# adc.net
KiCad netlist of a schematic drawn in Altium Designer
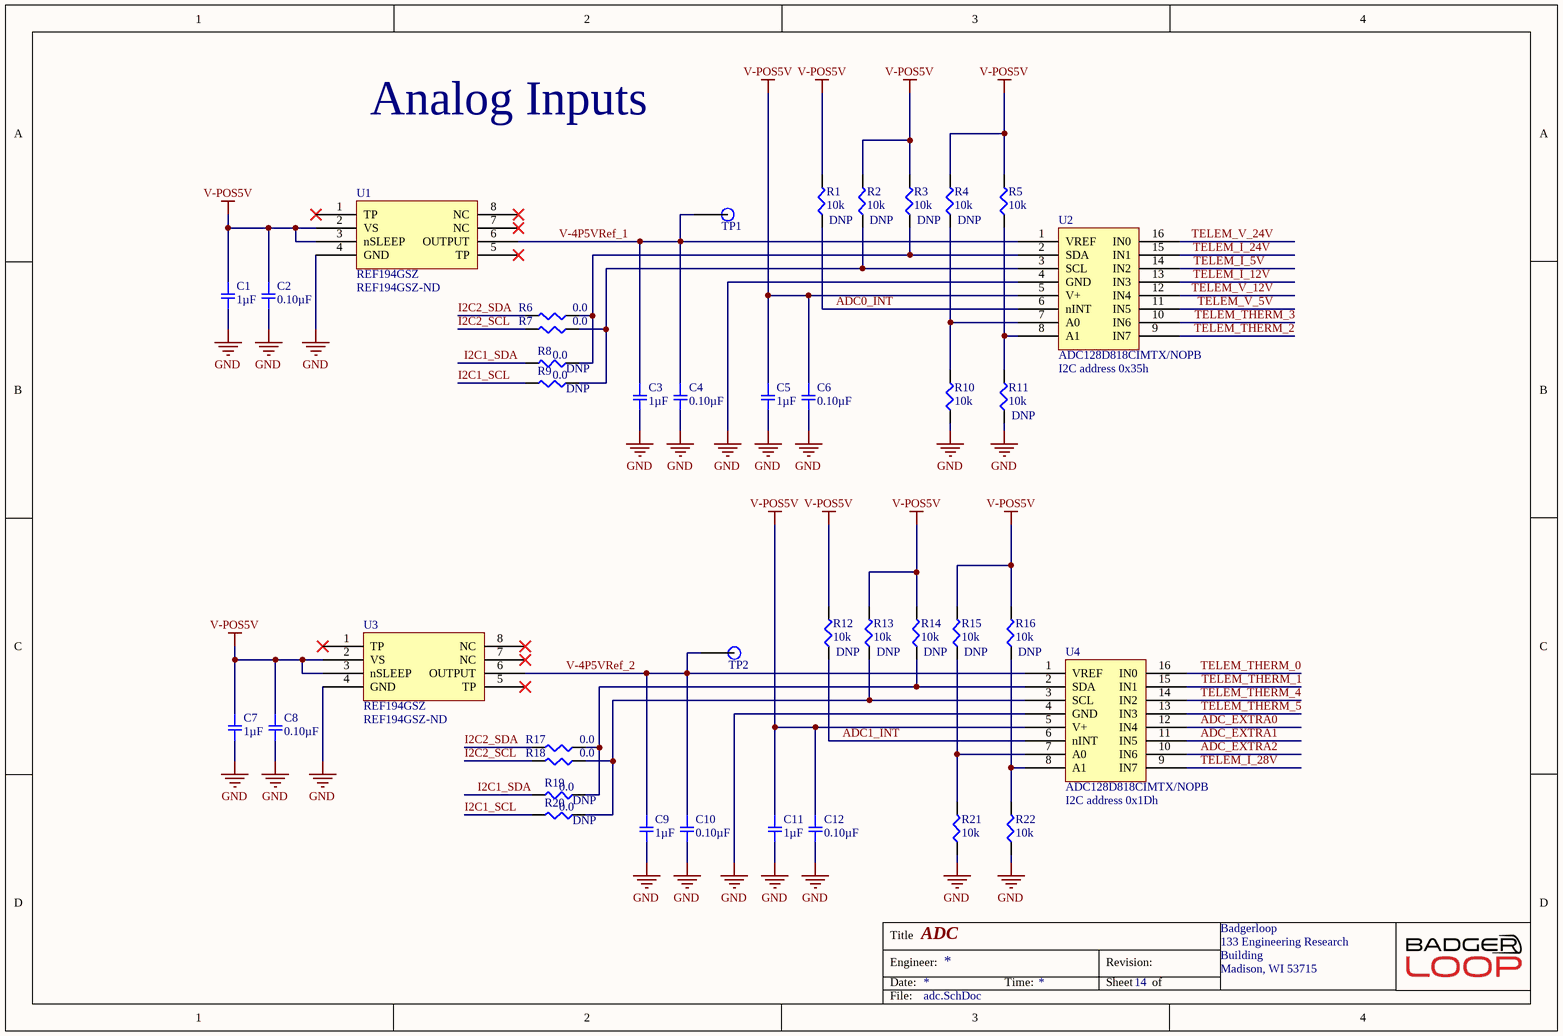
[diagram p0: adc.SchDoc]

(export (version "E")
  (design (tool "Eeschema 10.0.6"))
  (components
    (comp (ref "C1")
      (value "1µF")
      (footprint "SMD-0805C")
      (description "CAP CER 1UF 50V X7R 0805")
      (fields
        (field (name "DIGI-KEY PART NUMBER") "490-4736-1-ND")
        (field (name "PART NUMBER") "GRM21BR71H105KA12L")
      )
      (libsource (lib "capacitors") (part "GRM21BR71H105KA12L"))
    )
    (comp (ref "C2")
      (value "0.10µF")
      (footprint "SMD-0805C")
      (description "CAP CER 0.1UF 50V X7R 0805")
      (fields
        (field (name "DIGI-KEY PART NUMBER") "490-11955-1-ND")
        (field (name "PART NUMBER") "GCD21BR71H104KA01L")
      )
      (libsource (lib "capacitors") (part "GCD21BR71H104KA01L"))
    )
    (comp (ref "C3")
      (value "1µF")
      (footprint "SMD-0805C")
      (description "CAP CER 1UF 50V X7R 0805")
      (fields
        (field (name "DIGI-KEY PART NUMBER") "490-4736-1-ND")
        (field (name "PART NUMBER") "GRM21BR71H105KA12L")
      )
      (libsource (lib "capacitors") (part "GRM21BR71H105KA12L"))
    )
    (comp (ref "C4")
      (value "0.10µF")
      (footprint "SMD-0805C")
      (description "CAP CER 0.1UF 50V X7R 0805")
      (fields
        (field (name "DIGI-KEY PART NUMBER") "490-11955-1-ND")
        (field (name "PART NUMBER") "GCD21BR71H104KA01L")
      )
      (libsource (lib "capacitors") (part "GCD21BR71H104KA01L"))
    )
    (comp (ref "C5")
      (value "1µF")
      (footprint "SMD-0805C")
      (description "CAP CER 1UF 50V X7R 0805")
      (fields
        (field (name "DIGI-KEY PART NUMBER") "490-4736-1-ND")
        (field (name "PART NUMBER") "GRM21BR71H105KA12L")
      )
      (libsource (lib "capacitors") (part "GRM21BR71H105KA12L"))
    )
    (comp (ref "C6")
      (value "0.10µF")
      (footprint "SMD-0805C")
      (description "CAP CER 0.1UF 50V X7R 0805")
      (fields
        (field (name "DIGI-KEY PART NUMBER") "490-11955-1-ND")
        (field (name "PART NUMBER") "GCD21BR71H104KA01L")
      )
      (libsource (lib "capacitors") (part "GCD21BR71H104KA01L"))
    )
    (comp (ref "C7")
      (value "1µF")
      (footprint "SMD-0805C")
      (description "CAP CER 1UF 50V X7R 0805")
      (fields
        (field (name "DIGI-KEY PART NUMBER") "490-4736-1-ND")
        (field (name "PART NUMBER") "GRM21BR71H105KA12L")
      )
      (libsource (lib "capacitors") (part "GRM21BR71H105KA12L"))
    )
    (comp (ref "C8")
      (value "0.10µF")
      (footprint "SMD-0805C")
      (description "CAP CER 0.1UF 50V X7R 0805")
      (fields
        (field (name "DIGI-KEY PART NUMBER") "490-11955-1-ND")
        (field (name "PART NUMBER") "GCD21BR71H104KA01L")
      )
      (libsource (lib "capacitors") (part "GCD21BR71H104KA01L"))
    )
    (comp (ref "C9")
      (value "1µF")
      (footprint "SMD-0805C")
      (description "CAP CER 1UF 50V X7R 0805")
      (fields
        (field (name "DIGI-KEY PART NUMBER") "490-4736-1-ND")
        (field (name "PART NUMBER") "GRM21BR71H105KA12L")
      )
      (libsource (lib "capacitors") (part "GRM21BR71H105KA12L"))
    )
    (comp (ref "C10")
      (value "0.10µF")
      (footprint "SMD-0805C")
      (description "CAP CER 0.1UF 50V X7R 0805")
      (fields
        (field (name "DIGI-KEY PART NUMBER") "490-11955-1-ND")
        (field (name "PART NUMBER") "GCD21BR71H104KA01L")
      )
      (libsource (lib "capacitors") (part "GCD21BR71H104KA01L"))
    )
    (comp (ref "C11")
      (value "1µF")
      (footprint "SMD-0805C")
      (description "CAP CER 1UF 50V X7R 0805")
      (fields
        (field (name "DIGI-KEY PART NUMBER") "490-4736-1-ND")
        (field (name "PART NUMBER") "GRM21BR71H105KA12L")
      )
      (libsource (lib "capacitors") (part "GRM21BR71H105KA12L"))
    )
    (comp (ref "C12")
      (value "0.10µF")
      (footprint "SMD-0805C")
      (description "CAP CER 0.1UF 50V X7R 0805")
      (fields
        (field (name "DIGI-KEY PART NUMBER") "490-11955-1-ND")
        (field (name "PART NUMBER") "GCD21BR71H104KA01L")
      )
      (libsource (lib "capacitors") (part "GCD21BR71H104KA01L"))
    )
    (comp (ref "R1")
      (value "10k")
      (footprint "SMD-0805-RES")
      (description "RES SMD 10K OHM 5% 1/2W 0805")
      (fields
        (field (name "PART NUMBER") "ERJ-P06J103V")
        (field (name "DIGI-KEY PART NUMBER") "P10KADCT-ND")
        (field (name "DNP") "DNP")
      )
      (libsource (lib "resistors") (part "ERJ-P06J103V"))
    )
    (comp (ref "R2")
      (value "10k")
      (footprint "SMD-0805-RES")
      (description "RES SMD 10K OHM 5% 1/2W 0805")
      (fields
        (field (name "PART NUMBER") "ERJ-P06J103V")
        (field (name "DIGI-KEY PART NUMBER") "P10KADCT-ND")
        (field (name "DNP") "DNP")
      )
      (libsource (lib "resistors") (part "ERJ-P06J103V"))
    )
    (comp (ref "R3")
      (value "10k")
      (footprint "SMD-0805-RES")
      (description "RES SMD 10K OHM 5% 1/2W 0805")
      (fields
        (field (name "PART NUMBER") "ERJ-P06J103V")
        (field (name "DIGI-KEY PART NUMBER") "P10KADCT-ND")
        (field (name "DNP") "DNP")
      )
      (libsource (lib "resistors") (part "ERJ-P06J103V"))
    )
    (comp (ref "R4")
      (value "10k")
      (footprint "SMD-0805-RES")
      (description "RES SMD 10K OHM 5% 1/2W 0805")
      (fields
        (field (name "PART NUMBER") "ERJ-P06J103V")
        (field (name "DIGI-KEY PART NUMBER") "P10KADCT-ND")
        (field (name "DNP") "DNP")
      )
      (libsource (lib "resistors") (part "ERJ-P06J103V"))
    )
    (comp (ref "R5")
      (value "10k")
      (footprint "SMD-0805-RES")
      (description "RES SMD 10K OHM 5% 1/2W 0805")
      (fields (field (name "PART NUMBER") "ERJ-P06J103V") (field (name "DIGI-KEY PART NUMBER") "P10KADCT-ND"))
      (libsource (lib "resistors") (part "ERJ-P06J103V"))
    )
    (comp (ref "R6")
      (value "0.0")
      (footprint "SMD-0805-RES")
      (description "RES SMD 0.0 OHM JUMPER 1/8W 0805")
      (fields (field (name "PART NUMBER") "ERJ-6GEY0R00V") (field (name "DIGI-KEY PART NUMBER") "P0.0ACT-ND"))
      (libsource (lib "resistors") (part "ERJ-6GEY0R00V"))
    )
    (comp (ref "R7")
      (value "0.0")
      (footprint "SMD-0805-RES")
      (description "RES SMD 0.0 OHM JUMPER 1/8W 0805")
      (fields (field (name "PART NUMBER") "ERJ-6GEY0R00V") (field (name "DIGI-KEY PART NUMBER") "P0.0ACT-ND"))
      (libsource (lib "resistors") (part "ERJ-6GEY0R00V"))
    )
    (comp (ref "R8")
      (value "0.0")
      (footprint "SMD-0805-RES")
      (description "RES SMD 0.0 OHM JUMPER 1/8W 0805")
      (fields
        (field (name "PART NUMBER") "ERJ-6GEY0R00V")
        (field (name "DIGI-KEY PART NUMBER") "P0.0ACT-ND")
        (field (name "DNP") "DNP")
      )
      (libsource (lib "resistors") (part "ERJ-6GEY0R00V"))
    )
    (comp (ref "R9")
      (value "0.0")
      (footprint "SMD-0805-RES")
      (description "RES SMD 0.0 OHM JUMPER 1/8W 0805")
      (fields
        (field (name "PART NUMBER") "ERJ-6GEY0R00V")
        (field (name "DIGI-KEY PART NUMBER") "P0.0ACT-ND")
        (field (name "DNP") "DNP")
      )
      (libsource (lib "resistors") (part "ERJ-6GEY0R00V"))
    )
    (comp (ref "R10")
      (value "10k")
      (footprint "SMD-0805-RES")
      (description "RES SMD 10K OHM 5% 1/2W 0805")
      (fields (field (name "PART NUMBER") "ERJ-P06J103V") (field (name "DIGI-KEY PART NUMBER") "P10KADCT-ND"))
      (libsource (lib "resistors") (part "ERJ-P06J103V"))
    )
    (comp (ref "R11")
      (value "10k")
      (footprint "SMD-0805-RES")
      (description "RES SMD 10K OHM 5% 1/2W 0805")
      (fields
        (field (name "PART NUMBER") "ERJ-P06J103V")
        (field (name "DIGI-KEY PART NUMBER") "P10KADCT-ND")
        (field (name "DNP") "DNP")
      )
      (libsource (lib "resistors") (part "ERJ-P06J103V"))
    )
    (comp (ref "R12")
      (value "10k")
      (footprint "SMD-0805-RES")
      (description "RES SMD 10K OHM 5% 1/2W 0805")
      (fields
        (field (name "PART NUMBER") "ERJ-P06J103V")
        (field (name "DIGI-KEY PART NUMBER") "P10KADCT-ND")
        (field (name "DNP") "DNP")
      )
      (libsource (lib "resistors") (part "ERJ-P06J103V"))
    )
    (comp (ref "R13")
      (value "10k")
      (footprint "SMD-0805-RES")
      (description "RES SMD 10K OHM 5% 1/2W 0805")
      (fields
        (field (name "PART NUMBER") "ERJ-P06J103V")
        (field (name "DIGI-KEY PART NUMBER") "P10KADCT-ND")
        (field (name "DNP") "DNP")
      )
      (libsource (lib "resistors") (part "ERJ-P06J103V"))
    )
    (comp (ref "R14")
      (value "10k")
      (footprint "SMD-0805-RES")
      (description "RES SMD 10K OHM 5% 1/2W 0805")
      (fields
        (field (name "PART NUMBER") "ERJ-P06J103V")
        (field (name "DIGI-KEY PART NUMBER") "P10KADCT-ND")
        (field (name "DNP") "DNP")
      )
      (libsource (lib "resistors") (part "ERJ-P06J103V"))
    )
    (comp (ref "R15")
      (value "10k")
      (footprint "SMD-0805-RES")
      (description "RES SMD 10K OHM 5% 1/2W 0805")
      (fields
        (field (name "PART NUMBER") "ERJ-P06J103V")
        (field (name "DIGI-KEY PART NUMBER") "P10KADCT-ND")
        (field (name "DNP") "DNP")
      )
      (libsource (lib "resistors") (part "ERJ-P06J103V"))
    )
    (comp (ref "R16")
      (value "10k")
      (footprint "SMD-0805-RES")
      (description "RES SMD 10K OHM 5% 1/2W 0805")
      (fields
        (field (name "PART NUMBER") "ERJ-P06J103V")
        (field (name "DIGI-KEY PART NUMBER") "P10KADCT-ND")
        (field (name "DNP") "DNP")
      )
      (libsource (lib "resistors") (part "ERJ-P06J103V"))
    )
    (comp (ref "R17")
      (value "0.0")
      (footprint "SMD-0805-RES")
      (description "RES SMD 0.0 OHM JUMPER 1/8W 0805")
      (fields (field (name "PART NUMBER") "ERJ-6GEY0R00V") (field (name "DIGI-KEY PART NUMBER") "P0.0ACT-ND"))
      (libsource (lib "resistors") (part "ERJ-6GEY0R00V"))
    )
    (comp (ref "R18")
      (value "0.0")
      (footprint "SMD-0805-RES")
      (description "RES SMD 0.0 OHM JUMPER 1/8W 0805")
      (fields (field (name "PART NUMBER") "ERJ-6GEY0R00V") (field (name "DIGI-KEY PART NUMBER") "P0.0ACT-ND"))
      (libsource (lib "resistors") (part "ERJ-6GEY0R00V"))
    )
    (comp (ref "R19")
      (value "0.0")
      (footprint "SMD-0805-RES")
      (description "RES SMD 0.0 OHM JUMPER 1/8W 0805")
      (fields
        (field (name "PART NUMBER") "ERJ-6GEY0R00V")
        (field (name "DIGI-KEY PART NUMBER") "P0.0ACT-ND")
        (field (name "DNP") "DNP")
      )
      (libsource (lib "resistors") (part "ERJ-6GEY0R00V"))
    )
    (comp (ref "R20")
      (value "0.0")
      (footprint "SMD-0805-RES")
      (description "RES SMD 0.0 OHM JUMPER 1/8W 0805")
      (fields
        (field (name "PART NUMBER") "ERJ-6GEY0R00V")
        (field (name "DIGI-KEY PART NUMBER") "P0.0ACT-ND")
        (field (name "DNP") "DNP")
      )
      (libsource (lib "resistors") (part "ERJ-6GEY0R00V"))
    )
    (comp (ref "R21")
      (value "10k")
      (footprint "SMD-0805-RES")
      (description "RES SMD 10K OHM 5% 1/2W 0805")
      (fields (field (name "PART NUMBER") "ERJ-P06J103V") (field (name "DIGI-KEY PART NUMBER") "P10KADCT-ND"))
      (libsource (lib "resistors") (part "ERJ-P06J103V"))
    )
    (comp (ref "R22")
      (value "10k")
      (footprint "SMD-0805-RES")
      (description "RES SMD 10K OHM 5% 1/2W 0805")
      (fields (field (name "PART NUMBER") "ERJ-P06J103V") (field (name "DIGI-KEY PART NUMBER") "P10KADCT-ND"))
      (libsource (lib "resistors") (part "ERJ-P06J103V"))
    )
    (comp (ref "TP1")
      (value "TP")
      (footprint "Test Point")
      (description "SMD TEST POINT")
      (libsource (lib "misc") (part "TP"))
    )
    (comp (ref "TP2")
      (value "TP")
      (footprint "Test Point")
      (description "SMD TEST POINT")
      (libsource (lib "misc") (part "TP"))
    )
    (comp (ref "U1")
      (value "REF194GSZ")
      (footprint "SOP127P600X175-8N")
      (description "IC VREF SERIES 4.5V 8SOIC")
      (fields
        (field (name "MANUFACTURER") "Analog Devices")
        (field (name "SUPPLIER PART NUMBER 1") "REF194GSZ-ND")
      )
      (libsource (lib "ic") (part "REF194GSZ"))
    )
    (comp (ref "U2")
      (value "ADC128D818CIMTX/NOPB")
      (footprint "TSOP65P660X120-16N")
      (description "Analog to Digital Converters - ADC")
      (fields (field (name "MANUFACTURER") "TI National Semiconductor"))
      (libsource (lib "ic") (part "ADC128D818CIMTX/NOPB"))
    )
    (comp (ref "U3")
      (value "REF194GSZ")
      (footprint "SOP127P600X175-8N")
      (description "IC VREF SERIES 4.5V 8SOIC")
      (fields
        (field (name "MANUFACTURER") "Analog Devices")
        (field (name "SUPPLIER PART NUMBER 1") "REF194GSZ-ND")
      )
      (libsource (lib "ic") (part "REF194GSZ"))
    )
    (comp (ref "U4")
      (value "ADC128D818CIMTX/NOPB")
      (footprint "TSOP65P660X120-16N")
      (description "Analog to Digital Converters - ADC")
      (fields (field (name "MANUFACTURER") "TI National Semiconductor"))
      (libsource (lib "ic") (part "ADC128D818CIMTX/NOPB"))
    )
  )
  (nets
    (net (code "1") (name "/ADC0_INT") (class "Default")
      (node (ref "R1") (pin "1") (pinfunction "1_1") (pintype "passive"))
      (node (ref "U2") (pin "6") (pinfunction "nINT_6") (pintype "passive"))
    )
    (net (code "2") (name "/ADC1_INT") (class "Default")
      (node (ref "R12") (pin "1") (pinfunction "1_1") (pintype "passive"))
      (node (ref "U4") (pin "6") (pinfunction "nINT_6") (pintype "passive"))
    )
    (net (code "3") (name "/ADC_EXTRA0") (class "Default")
      (node (ref "U4") (pin "12") (pinfunction "IN4_12") (pintype "passive"))
    )
    (net (code "4") (name "/ADC_EXTRA1") (class "Default")
      (node (ref "U4") (pin "11") (pinfunction "IN5_11") (pintype "passive"))
    )
    (net (code "5") (name "/ADC_EXTRA2") (class "Default")
      (node (ref "U4") (pin "10") (pinfunction "IN6_10") (pintype "passive"))
    )
    (net (code "6") (name "/I2C1_SCL") (class "Default")
      (node (ref "R20") (pin "2") (pinfunction "2_2") (pintype "passive"))
      (node (ref "R9") (pin "2") (pinfunction "2_2") (pintype "passive"))
    )
    (net (code "7") (name "/I2C1_SDA") (class "Default")
      (node (ref "R19") (pin "2") (pinfunction "2_2") (pintype "passive"))
      (node (ref "R8") (pin "2") (pinfunction "2_2") (pintype "passive"))
    )
    (net (code "8") (name "/I2C2_SCL") (class "Default")
      (node (ref "R18") (pin "2") (pinfunction "2_2") (pintype "passive"))
      (node (ref "R7") (pin "2") (pinfunction "2_2") (pintype "passive"))
    )
    (net (code "9") (name "/I2C2_SDA") (class "Default")
      (node (ref "R17") (pin "2") (pinfunction "2_2") (pintype "passive"))
      (node (ref "R6") (pin "2") (pinfunction "2_2") (pintype "passive"))
    )
    (net (code "10") (name "/TELEM_I_5V") (class "Default")
      (node (ref "U2") (pin "14") (pinfunction "IN2_14") (pintype "passive"))
    )
    (net (code "11") (name "/TELEM_I_12V") (class "Default")
      (node (ref "U2") (pin "13") (pinfunction "IN3_13") (pintype "passive"))
    )
    (net (code "12") (name "/TELEM_I_24V") (class "Default")
      (node (ref "U2") (pin "15") (pinfunction "IN1_15") (pintype "passive"))
    )
    (net (code "13") (name "/TELEM_I_28V") (class "Default")
      (node (ref "U4") (pin "9") (pinfunction "IN7_9") (pintype "passive"))
    )
    (net (code "14") (name "/TELEM_THERM_0") (class "Default")
      (node (ref "U4") (pin "16") (pinfunction "IN0_16") (pintype "passive"))
    )
    (net (code "15") (name "/TELEM_THERM_1") (class "Default")
      (node (ref "U4") (pin "15") (pinfunction "IN1_15") (pintype "passive"))
    )
    (net (code "16") (name "/TELEM_THERM_2") (class "Default")
      (node (ref "U2") (pin "9") (pinfunction "IN7_9") (pintype "passive"))
    )
    (net (code "17") (name "/TELEM_THERM_3") (class "Default")
      (node (ref "U2") (pin "10") (pinfunction "IN6_10") (pintype "passive"))
    )
    (net (code "18") (name "/TELEM_THERM_4") (class "Default")
      (node (ref "U4") (pin "14") (pinfunction "IN2_14") (pintype "passive"))
    )
    (net (code "19") (name "/TELEM_THERM_5") (class "Default")
      (node (ref "U4") (pin "13") (pinfunction "IN3_13") (pintype "passive"))
    )
    (net (code "20") (name "/TELEM_V_5V") (class "Default")
      (node (ref "U2") (pin "11") (pinfunction "IN5_11") (pintype "passive"))
    )
    (net (code "21") (name "/TELEM_V_12V") (class "Default")
      (node (ref "U2") (pin "12") (pinfunction "IN4_12") (pintype "passive"))
    )
    (net (code "22") (name "/TELEM_V_24V") (class "Default")
      (node (ref "U2") (pin "16") (pinfunction "IN0_16") (pintype "passive"))
    )
    (net (code "23") (name "/V-4P5VRef_1") (class "Default")
      (node (ref "C3") (pin "1") (pinfunction "1_1") (pintype "passive"))
      (node (ref "C4") (pin "1") (pinfunction "1_1") (pintype "passive"))
      (node (ref "TP1") (pin "1") (pinfunction "1_1") (pintype "passive"))
      (node (ref "U1") (pin "6") (pinfunction "OUTPUT_6") (pintype "passive"))
      (node (ref "U2") (pin "1") (pinfunction "VREF_1") (pintype "passive"))
    )
    (net (code "24") (name "/V-4P5VRef_2") (class "Default")
      (node (ref "C10") (pin "1") (pinfunction "1_1") (pintype "passive"))
      (node (ref "C9") (pin "1") (pinfunction "1_1") (pintype "passive"))
      (node (ref "TP2") (pin "1") (pinfunction "1_1") (pintype "passive"))
      (node (ref "U3") (pin "6") (pinfunction "OUTPUT_6") (pintype "passive"))
      (node (ref "U4") (pin "1") (pinfunction "VREF_1") (pintype "passive"))
    )
    (net (code "25") (name "GND") (class "Default")
      (node (ref "C1") (pin "2") (pinfunction "2_2") (pintype "passive"))
      (node (ref "C10") (pin "2") (pinfunction "2_2") (pintype "passive"))
      (node (ref "C11") (pin "2") (pinfunction "2_2") (pintype "passive"))
      (node (ref "C12") (pin "2") (pinfunction "2_2") (pintype "passive"))
      (node (ref "C2") (pin "2") (pinfunction "2_2") (pintype "passive"))
      (node (ref "C3") (pin "2") (pinfunction "2_2") (pintype "passive"))
      (node (ref "C4") (pin "2") (pinfunction "2_2") (pintype "passive"))
      (node (ref "C5") (pin "2") (pinfunction "2_2") (pintype "passive"))
      (node (ref "C6") (pin "2") (pinfunction "2_2") (pintype "passive"))
      (node (ref "C7") (pin "2") (pinfunction "2_2") (pintype "passive"))
      (node (ref "C8") (pin "2") (pinfunction "2_2") (pintype "passive"))
      (node (ref "C9") (pin "2") (pinfunction "2_2") (pintype "passive"))
      (node (ref "R10") (pin "1") (pinfunction "1_1") (pintype "passive"))
      (node (ref "R11") (pin "1") (pinfunction "1_1") (pintype "passive"))
      (node (ref "R21") (pin "1") (pinfunction "1_1") (pintype "passive"))
      (node (ref "R22") (pin "1") (pinfunction "1_1") (pintype "passive"))
      (node (ref "U1") (pin "4") (pinfunction "GND_4") (pintype "passive"))
      (node (ref "U2") (pin "4") (pinfunction "GND_4") (pintype "passive"))
      (node (ref "U3") (pin "4") (pinfunction "GND_4") (pintype "passive"))
      (node (ref "U4") (pin "4") (pinfunction "GND_4") (pintype "passive"))
    )
    (net (code "26") (name "Net-(U2-A0)") (class "Default")
      (node (ref "R10") (pin "2") (pinfunction "2_2") (pintype "passive"))
      (node (ref "R4") (pin "1") (pinfunction "1_1") (pintype "passive"))
      (node (ref "U2") (pin "7") (pinfunction "A0_7") (pintype "passive"))
    )
    (net (code "27") (name "Net-(U2-A1)") (class "Default")
      (node (ref "R11") (pin "2") (pinfunction "2_2") (pintype "passive"))
      (node (ref "R5") (pin "1") (pinfunction "1_1") (pintype "passive"))
      (node (ref "U2") (pin "8") (pinfunction "A1_8") (pintype "passive"))
    )
    (net (code "28") (name "Net-(U2-SCL)") (class "Default")
      (node (ref "R2") (pin "1") (pinfunction "1_1") (pintype "passive"))
      (node (ref "R7") (pin "1") (pinfunction "1_1") (pintype "passive"))
      (node (ref "R9") (pin "1") (pinfunction "1_1") (pintype "passive"))
      (node (ref "U2") (pin "3") (pinfunction "SCL_3") (pintype "passive"))
    )
    (net (code "29") (name "Net-(U2-SDA)") (class "Default")
      (node (ref "R3") (pin "1") (pinfunction "1_1") (pintype "passive"))
      (node (ref "R6") (pin "1") (pinfunction "1_1") (pintype "passive"))
      (node (ref "R8") (pin "1") (pinfunction "1_1") (pintype "passive"))
      (node (ref "U2") (pin "2") (pinfunction "SDA_2") (pintype "passive"))
    )
    (net (code "30") (name "Net-(U4-A0)") (class "Default")
      (node (ref "R15") (pin "1") (pinfunction "1_1") (pintype "passive"))
      (node (ref "R21") (pin "2") (pinfunction "2_2") (pintype "passive"))
      (node (ref "U4") (pin "7") (pinfunction "A0_7") (pintype "passive"))
    )
    (net (code "31") (name "Net-(U4-A1)") (class "Default")
      (node (ref "R16") (pin "1") (pinfunction "1_1") (pintype "passive"))
      (node (ref "R22") (pin "2") (pinfunction "2_2") (pintype "passive"))
      (node (ref "U4") (pin "8") (pinfunction "A1_8") (pintype "passive"))
    )
    (net (code "32") (name "Net-(U4-SCL)") (class "Default")
      (node (ref "R13") (pin "1") (pinfunction "1_1") (pintype "passive"))
      (node (ref "R18") (pin "1") (pinfunction "1_1") (pintype "passive"))
      (node (ref "R20") (pin "1") (pinfunction "1_1") (pintype "passive"))
      (node (ref "U4") (pin "3") (pinfunction "SCL_3") (pintype "passive"))
    )
    (net (code "33") (name "Net-(U4-SDA)") (class "Default")
      (node (ref "R14") (pin "1") (pinfunction "1_1") (pintype "passive"))
      (node (ref "R17") (pin "1") (pinfunction "1_1") (pintype "passive"))
      (node (ref "R19") (pin "1") (pinfunction "1_1") (pintype "passive"))
      (node (ref "U4") (pin "2") (pinfunction "SDA_2") (pintype "passive"))
    )
    (net (code "34") (name "V-POS5V") (class "Default")
      (node (ref "C1") (pin "1") (pinfunction "1_1") (pintype "passive"))
      (node (ref "C11") (pin "1") (pinfunction "1_1") (pintype "passive"))
      (node (ref "C12") (pin "1") (pinfunction "1_1") (pintype "passive"))
      (node (ref "C2") (pin "1") (pinfunction "1_1") (pintype "passive"))
      (node (ref "C5") (pin "1") (pinfunction "1_1") (pintype "passive"))
      (node (ref "C6") (pin "1") (pinfunction "1_1") (pintype "passive"))
      (node (ref "C7") (pin "1") (pinfunction "1_1") (pintype "passive"))
      (node (ref "C8") (pin "1") (pinfunction "1_1") (pintype "passive"))
      (node (ref "R1") (pin "2") (pinfunction "2_2") (pintype "passive"))
      (node (ref "R12") (pin "2") (pinfunction "2_2") (pintype "passive"))
      (node (ref "R13") (pin "2") (pinfunction "2_2") (pintype "passive"))
      (node (ref "R14") (pin "2") (pinfunction "2_2") (pintype "passive"))
      (node (ref "R15") (pin "2") (pinfunction "2_2") (pintype "passive"))
      (node (ref "R16") (pin "2") (pinfunction "2_2") (pintype "passive"))
      (node (ref "R2") (pin "2") (pinfunction "2_2") (pintype "passive"))
      (node (ref "R3") (pin "2") (pinfunction "2_2") (pintype "passive"))
      (node (ref "R4") (pin "2") (pinfunction "2_2") (pintype "passive"))
      (node (ref "R5") (pin "2") (pinfunction "2_2") (pintype "passive"))
      (node (ref "U1") (pin "2") (pinfunction "VS_2") (pintype "passive"))
      (node (ref "U1") (pin "3") (pinfunction "nSLEEP_3") (pintype "passive"))
      (node (ref "U2") (pin "5") (pinfunction "V+_5") (pintype "passive"))
      (node (ref "U3") (pin "2") (pinfunction "VS_2") (pintype "passive"))
      (node (ref "U3") (pin "3") (pinfunction "nSLEEP_3") (pintype "passive"))
      (node (ref "U4") (pin "5") (pinfunction "V+_5") (pintype "passive"))
    )
    (net (code "35") (name "unconnected-(U1-NC-Pad7)") (class "Default")
      (node (ref "U1") (pin "7") (pinfunction "NC_7") (pintype "passive+no_connect"))
    )
    (net (code "36") (name "unconnected-(U1-NC-Pad8)") (class "Default")
      (node (ref "U1") (pin "8") (pinfunction "NC_8") (pintype "passive+no_connect"))
    )
    (net (code "37") (name "unconnected-(U1-TP-Pad1)") (class "Default")
      (node (ref "U1") (pin "1") (pinfunction "TP_1") (pintype "passive+no_connect"))
    )
    (net (code "38") (name "unconnected-(U1-TP-Pad5)") (class "Default")
      (node (ref "U1") (pin "5") (pinfunction "TP_5") (pintype "passive+no_connect"))
    )
    (net (code "39") (name "unconnected-(U3-NC-Pad7)") (class "Default")
      (node (ref "U3") (pin "7") (pinfunction "NC_7") (pintype "passive+no_connect"))
    )
    (net (code "40") (name "unconnected-(U3-NC-Pad8)") (class "Default")
      (node (ref "U3") (pin "8") (pinfunction "NC_8") (pintype "passive+no_connect"))
    )
    (net (code "41") (name "unconnected-(U3-TP-Pad1)") (class "Default")
      (node (ref "U3") (pin "1") (pinfunction "TP_1") (pintype "passive+no_connect"))
    )
    (net (code "42") (name "unconnected-(U3-TP-Pad5)") (class "Default")
      (node (ref "U3") (pin "5") (pinfunction "TP_5") (pintype "passive+no_connect"))
    )
  )
)
